# CAN_HB_PV_Heatpump.net
KiCad netlist of a schematic drawn in EAGLE
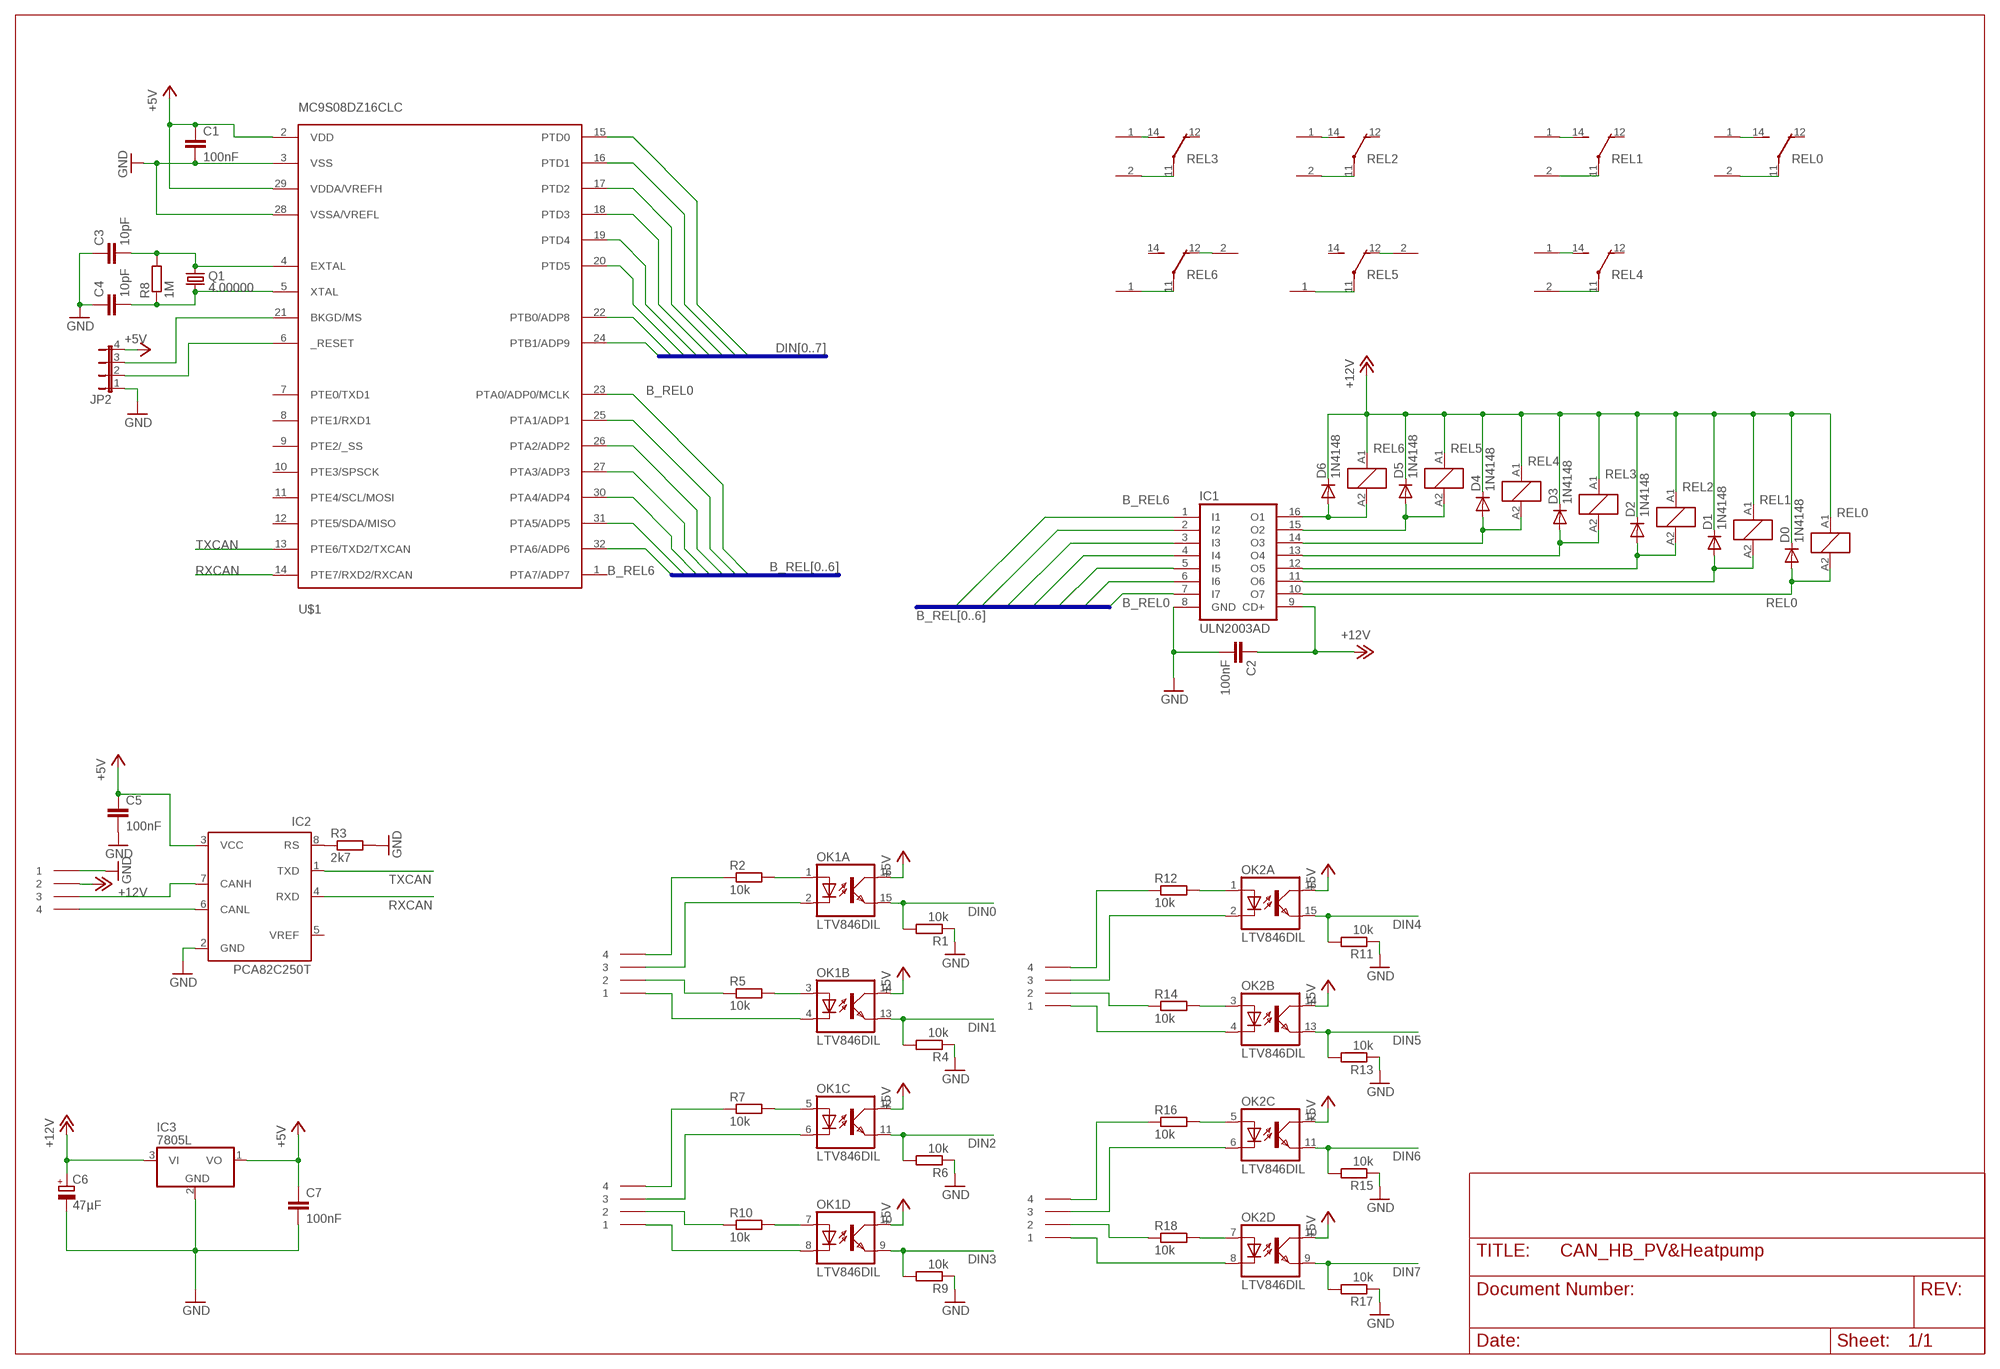
[diagram p0: schematic, sheet 1]

(export (version "E")
  (design (tool "Eeschema 10.0.6"))
  (components
    (comp (ref "C1")
      (value "100nF")
      (footprint "eagle-import:C0805K")
      (libsource (lib "eagle-import") (part "C-EUC0805K"))
    )
    (comp (ref "C2")
      (value "100nF")
      (footprint "eagle-import:C0805")
      (libsource (lib "eagle-import") (part "rcl_334_C-EUC0805"))
    )
    (comp (ref "C3")
      (value "10pF")
      (footprint "eagle-import:C0805K")
      (libsource (lib "eagle-import") (part "C-EUC0805K"))
    )
    (comp (ref "C4")
      (value "10pF")
      (footprint "eagle-import:C0805K")
      (libsource (lib "eagle-import") (part "C-EUC0805K"))
    )
    (comp (ref "C5")
      (value "100nF")
      (footprint "eagle-import:C0805")
      (libsource (lib "eagle-import") (part "C-EUC0805"))
    )
    (comp (ref "C6")
      (value "47µF")
      (footprint "eagle-import:E2-5")
      (libsource (lib "eagle-import") (part "CPOL-EUE2-5"))
    )
    (comp (ref "C7")
      (value "100nF")
      (footprint "eagle-import:C0805K")
      (libsource (lib "eagle-import") (part "C-EUC0805K"))
    )
    (comp (ref "D0")
      (value "1N4148")
      (footprint "eagle-import:SOD80C")
      (libsource (lib "eagle-import") (part "DIODE-SOD80C"))
    )
    (comp (ref "D1")
      (value "1N4148")
      (footprint "eagle-import:SOD80C")
      (libsource (lib "eagle-import") (part "DIODE-SOD80C"))
    )
    (comp (ref "D2")
      (value "1N4148")
      (footprint "eagle-import:SOD80C")
      (libsource (lib "eagle-import") (part "DIODE-SOD80C"))
    )
    (comp (ref "D3")
      (value "1N4148")
      (footprint "eagle-import:SOD80C")
      (libsource (lib "eagle-import") (part "DIODE-SOD80C"))
    )
    (comp (ref "D4")
      (value "1N4148")
      (footprint "eagle-import:SOD80C")
      (libsource (lib "eagle-import") (part "DIODE-SOD80C"))
    )
    (comp (ref "D5")
      (value "1N4148")
      (footprint "eagle-import:SOD80C")
      (libsource (lib "eagle-import") (part "DIODE-SOD80C"))
    )
    (comp (ref "D6")
      (value "1N4148")
      (footprint "eagle-import:SOD80C")
      (libsource (lib "eagle-import") (part "DIODE-SOD80C"))
    )
    (comp (ref "IC1")
      (value "ULN2003AD")
      (footprint "eagle-import:SO16")
      (libsource (lib "eagle-import") (part "ULN2003AD"))
    )
    (comp (ref "IC2")
      (value "PCA82C250T")
      (footprint "eagle-import:SO8")
      (libsource (lib "eagle-import") (part "PCA82C250T"))
    )
    (comp (ref "IC3")
      (value "7805L")
      (footprint "eagle-import:TO92")
      (libsource (lib "eagle-import") (part "78L05"))
    )
    (comp (ref "JP2")
      (value "JP4E")
      (footprint "eagle-import:JP4")
      (libsource (lib "eagle-import") (part "JP4E"))
    )
    (comp (ref "KL1")
      (value "AST021-04")
      (footprint "eagle-import:AST021-04")
      (libsource (lib "eagle-import") (part "AST021-04"))
    )
    (comp (ref "KL2")
      (value "AST021-04")
      (footprint "eagle-import:AST021-04")
      (libsource (lib "eagle-import") (part "AST021-04"))
    )
    (comp (ref "KL3")
      (value "AST021-04")
      (footprint "eagle-import:AST021-04")
      (libsource (lib "eagle-import") (part "AST021-04"))
    )
    (comp (ref "KL4")
      (value "AST021-04")
      (footprint "eagle-import:AST021-04")
      (libsource (lib "eagle-import") (part "AST021-04"))
    )
    (comp (ref "KL5")
      (value "AST021-04")
      (footprint "eagle-import:AST021-04")
      (libsource (lib "eagle-import") (part "AST021-04"))
    )
    (comp (ref "OK1")
      (value "LTV846DIL")
      (footprint "eagle-import:DIL16")
      (libsource (lib "eagle-import") (part "LTV846DIL"))
    )
    (comp (ref "OK2")
      (value "LTV846DIL")
      (footprint "eagle-import:DIL16")
      (libsource (lib "eagle-import") (part "LTV846DIL"))
    )
    (comp (ref "Q1")
      (value "4.00000")
      (footprint "eagle-import:HC49U-V")
      (libsource (lib "eagle-import") (part "CRYTALHC49U-V"))
    )
    (comp (ref "R1")
      (value "10k")
      (footprint "eagle-import:R0805")
      (libsource (lib "eagle-import") (part "rcl_334_R-EU_R0805"))
    )
    (comp (ref "R2")
      (value "10k")
      (footprint "eagle-import:R0805")
      (libsource (lib "eagle-import") (part "rcl_334_R-EU_R0805"))
    )
    (comp (ref "R3")
      (value "2k7")
      (footprint "eagle-import:R0805")
      (libsource (lib "eagle-import") (part "R-EU_R0805"))
    )
    (comp (ref "R4")
      (value "10k")
      (footprint "eagle-import:R0805")
      (libsource (lib "eagle-import") (part "rcl_334_R-EU_R0805"))
    )
    (comp (ref "R5")
      (value "10k")
      (footprint "eagle-import:R0805")
      (libsource (lib "eagle-import") (part "rcl_334_R-EU_R0805"))
    )
    (comp (ref "R6")
      (value "10k")
      (footprint "eagle-import:R0805")
      (libsource (lib "eagle-import") (part "rcl_334_R-EU_R0805"))
    )
    (comp (ref "R7")
      (value "10k")
      (footprint "eagle-import:R0805")
      (libsource (lib "eagle-import") (part "rcl_334_R-EU_R0805"))
    )
    (comp (ref "R8")
      (value "1M")
      (footprint "eagle-import:R0805")
      (libsource (lib "eagle-import") (part "R-EU_R0805"))
    )
    (comp (ref "R9")
      (value "10k")
      (footprint "eagle-import:R0805")
      (libsource (lib "eagle-import") (part "rcl_334_R-EU_R0805"))
    )
    (comp (ref "R10")
      (value "10k")
      (footprint "eagle-import:R0805")
      (libsource (lib "eagle-import") (part "rcl_334_R-EU_R0805"))
    )
    (comp (ref "R11")
      (value "10k")
      (footprint "eagle-import:R0805")
      (libsource (lib "eagle-import") (part "rcl_334_R-EU_R0805"))
    )
    (comp (ref "R12")
      (value "10k")
      (footprint "eagle-import:R0805")
      (libsource (lib "eagle-import") (part "rcl_334_R-EU_R0805"))
    )
    (comp (ref "R13")
      (value "10k")
      (footprint "eagle-import:R0805")
      (libsource (lib "eagle-import") (part "rcl_334_R-EU_R0805"))
    )
    (comp (ref "R14")
      (value "10k")
      (footprint "eagle-import:R0805")
      (libsource (lib "eagle-import") (part "rcl_334_R-EU_R0805"))
    )
    (comp (ref "R15")
      (value "10k")
      (footprint "eagle-import:R0805")
      (libsource (lib "eagle-import") (part "rcl_334_R-EU_R0805"))
    )
    (comp (ref "R16")
      (value "10k")
      (footprint "eagle-import:R0805")
      (libsource (lib "eagle-import") (part "rcl_334_R-EU_R0805"))
    )
    (comp (ref "R17")
      (value "10k")
      (footprint "eagle-import:R0805")
      (libsource (lib "eagle-import") (part "rcl_334_R-EU_R0805"))
    )
    (comp (ref "R18")
      (value "10k")
      (footprint "eagle-import:R0805")
      (libsource (lib "eagle-import") (part "rcl_334_R-EU_R0805"))
    )
    (comp (ref "REL0")
      (value "FIN34.51FIN34.51.7")
      (footprint "eagle-import:FIN34")
      (libsource (lib "eagle-import") (part "FIN34.51FIN34.51.7"))
    )
    (comp (ref "REL1")
      (value "FIN34.51FIN34.51.7")
      (footprint "eagle-import:FIN34")
      (libsource (lib "eagle-import") (part "FIN34.51FIN34.51.7"))
    )
    (comp (ref "REL2")
      (value "FIN34.51FIN34.51.7")
      (footprint "eagle-import:FIN34")
      (libsource (lib "eagle-import") (part "FIN34.51FIN34.51.7"))
    )
    (comp (ref "REL3")
      (value "FIN34.51FIN34.51.7")
      (footprint "eagle-import:FIN34")
      (libsource (lib "eagle-import") (part "FIN34.51FIN34.51.7"))
    )
    (comp (ref "REL4")
      (value "FIN34.51FIN34.51.7")
      (footprint "eagle-import:FIN34")
      (libsource (lib "eagle-import") (part "FIN34.51FIN34.51.7"))
    )
    (comp (ref "REL5")
      (value "FIN34.51FIN34.51.7")
      (footprint "eagle-import:FIN34")
      (libsource (lib "eagle-import") (part "FIN34.51FIN34.51.7"))
    )
    (comp (ref "REL6")
      (value "FIN34.51FIN34.51.7")
      (footprint "eagle-import:FIN34")
      (libsource (lib "eagle-import") (part "FIN34.51FIN34.51.7"))
    )
    (comp (ref "U$1")
      (value "MC9S08DZ16CLC")
      (footprint "eagle-import:LQFP32")
      (libsource (lib "eagle-import") (part "MC9S08DZ16CLC"))
    )
    (comp (ref "U$2")
      (value "AKL320-02")
      (footprint "eagle-import:AKL320-02")
      (libsource (lib "eagle-import") (part "AKL320-02"))
    )
    (comp (ref "U$3")
      (value "AKL320-02")
      (footprint "eagle-import:AKL320-02")
      (libsource (lib "eagle-import") (part "AKL320-02"))
    )
    (comp (ref "U$4")
      (value "AKL320-02")
      (footprint "eagle-import:AKL320-02")
      (libsource (lib "eagle-import") (part "AKL320-02"))
    )
    (comp (ref "U$5")
      (value "AKL320-02")
      (footprint "eagle-import:AKL320-02")
      (libsource (lib "eagle-import") (part "AKL320-02"))
    )
    (comp (ref "U$6")
      (value "AKL320-02")
      (footprint "eagle-import:AKL320-02")
      (libsource (lib "eagle-import") (part "AKL320-02"))
    )
    (comp (ref "U$14")
      (value "AKL320-02")
      (footprint "eagle-import:AKL320-02")
      (libsource (lib "eagle-import") (part "AKL320-02"))
    )
    (comp (ref "U$15")
      (value "AKL320-02")
      (footprint "eagle-import:AKL320-02")
      (libsource (lib "eagle-import") (part "AKL320-02"))
    )
  )
  (nets
    (net (code "1") (name "+5V") (class "Default")
      (node (ref "C1") (pin "1") (pinfunction "1_1") (pintype "passive"))
      (node (ref "C5") (pin "1") (pinfunction "1_1") (pintype "passive"))
      (node (ref "C7") (pin "1") (pinfunction "1_1") (pintype "passive"))
      (node (ref "IC2") (pin "3") (pinfunction "VCC_3") (pintype "power_in"))
      (node (ref "IC3") (pin "1") (pinfunction "VO_1") (pintype "passive"))
      (node (ref "JP2") (pin "4") (pinfunction "4_4") (pintype "passive"))
      (node (ref "OK1") (pin "10") (pinfunction "COL_10") (pintype "passive"))
      (node (ref "OK1") (pin "12") (pinfunction "COL_12") (pintype "passive"))
      (node (ref "OK1") (pin "14") (pinfunction "COL_14") (pintype "passive"))
      (node (ref "OK1") (pin "16") (pinfunction "COL_16") (pintype "passive"))
      (node (ref "OK2") (pin "10") (pinfunction "COL_10") (pintype "passive"))
      (node (ref "OK2") (pin "12") (pinfunction "COL_12") (pintype "passive"))
      (node (ref "OK2") (pin "14") (pinfunction "COL_14") (pintype "passive"))
      (node (ref "OK2") (pin "16") (pinfunction "COL_16") (pintype "passive"))
      (node (ref "U$1") (pin "2") (pinfunction "VDD_2") (pintype "power_in"))
      (node (ref "U$1") (pin "29") (pinfunction "VDDA/VREFH_29") (pintype "power_in"))
    )
    (net (code "2") (name "+12V") (class "Default")
      (node (ref "C2") (pin "1") (pinfunction "1_1") (pintype "passive"))
      (node (ref "C6") (pin "+") (pinfunction "+_+") (pintype "passive"))
      (node (ref "D0") (pin "C") (pinfunction "C_C") (pintype "passive"))
      (node (ref "D1") (pin "C") (pinfunction "C_C") (pintype "passive"))
      (node (ref "D2") (pin "C") (pinfunction "C_C") (pintype "passive"))
      (node (ref "D3") (pin "C") (pinfunction "C_C") (pintype "passive"))
      (node (ref "D4") (pin "C") (pinfunction "C_C") (pintype "passive"))
      (node (ref "D5") (pin "C") (pinfunction "C_C") (pintype "passive"))
      (node (ref "D6") (pin "C") (pinfunction "C_C") (pintype "passive"))
      (node (ref "IC1") (pin "9") (pinfunction "CD+_9") (pintype "passive"))
      (node (ref "IC3") (pin "3") (pinfunction "VI_3") (pintype "input"))
      (node (ref "KL1") (pin "P$2") (pinfunction "2_P$2") (pintype "bidirectional"))
      (node (ref "REL0") (pin "A1") (pinfunction "1_A1") (pintype "passive"))
      (node (ref "REL1") (pin "A1") (pinfunction "1_A1") (pintype "passive"))
      (node (ref "REL2") (pin "A1") (pinfunction "1_A1") (pintype "passive"))
      (node (ref "REL3") (pin "A1") (pinfunction "1_A1") (pintype "passive"))
      (node (ref "REL4") (pin "A1") (pinfunction "1_A1") (pintype "passive"))
      (node (ref "REL5") (pin "A1") (pinfunction "1_A1") (pintype "passive"))
      (node (ref "REL6") (pin "A1") (pinfunction "1_A1") (pintype "passive"))
    )
    (net (code "3") (name "/B_REL0") (class "Default")
      (node (ref "IC1") (pin "7") (pinfunction "I7_7") (pintype "input"))
      (node (ref "U$1") (pin "23") (pinfunction "PTA0/ADP0/MCLK_23") (pintype "bidirectional"))
    )
    (net (code "4") (name "/B_REL1") (class "Default")
      (node (ref "IC1") (pin "6") (pinfunction "I6_6") (pintype "input"))
      (node (ref "U$1") (pin "25") (pinfunction "PTA1/ADP1_25") (pintype "bidirectional"))
    )
    (net (code "5") (name "/B_REL2") (class "Default")
      (node (ref "IC1") (pin "5") (pinfunction "I5_5") (pintype "input"))
      (node (ref "U$1") (pin "26") (pinfunction "PTA2/ADP2_26") (pintype "bidirectional"))
    )
    (net (code "6") (name "/B_REL3") (class "Default")
      (node (ref "IC1") (pin "4") (pinfunction "I4_4") (pintype "input"))
      (node (ref "U$1") (pin "27") (pinfunction "PTA3/ADP3_27") (pintype "bidirectional"))
    )
    (net (code "7") (name "/B_REL4") (class "Default")
      (node (ref "IC1") (pin "3") (pinfunction "I3_3") (pintype "input"))
      (node (ref "U$1") (pin "30") (pinfunction "PTA4/ADP4_30") (pintype "bidirectional"))
    )
    (net (code "8") (name "/B_REL5") (class "Default")
      (node (ref "IC1") (pin "2") (pinfunction "I2_2") (pintype "input"))
      (node (ref "U$1") (pin "31") (pinfunction "PTA5/ADP5_31") (pintype "bidirectional"))
    )
    (net (code "9") (name "/B_REL6") (class "Default")
      (node (ref "IC1") (pin "1") (pinfunction "I1_1") (pintype "input"))
      (node (ref "U$1") (pin "32") (pinfunction "PTA6/ADP6_32") (pintype "bidirectional"))
    )
    (net (code "11") (name "/DIN0") (class "Default")
      (node (ref "OK1") (pin "15") (pinfunction "EMIT_15") (pintype "passive"))
      (node (ref "R1") (pin "2") (pinfunction "2_2") (pintype "passive"))
      (node (ref "U$1") (pin "15") (pinfunction "PTD0_15") (pintype "bidirectional"))
    )
    (net (code "12") (name "/DIN1") (class "Default")
      (node (ref "OK1") (pin "13") (pinfunction "EMIT_13") (pintype "passive"))
      (node (ref "R4") (pin "2") (pinfunction "2_2") (pintype "passive"))
      (node (ref "U$1") (pin "16") (pinfunction "PTD1_16") (pintype "bidirectional"))
    )
    (net (code "13") (name "/DIN2") (class "Default")
      (node (ref "OK1") (pin "11") (pinfunction "EMIT_11") (pintype "passive"))
      (node (ref "R6") (pin "2") (pinfunction "2_2") (pintype "passive"))
      (node (ref "U$1") (pin "17") (pinfunction "PTD2_17") (pintype "bidirectional"))
    )
    (net (code "14") (name "/DIN3") (class "Default")
      (node (ref "OK1") (pin "9") (pinfunction "EMIT_9") (pintype "passive"))
      (node (ref "R9") (pin "2") (pinfunction "2_2") (pintype "passive"))
      (node (ref "U$1") (pin "18") (pinfunction "PTD3_18") (pintype "bidirectional"))
    )
    (net (code "15") (name "/DIN4") (class "Default")
      (node (ref "OK2") (pin "15") (pinfunction "EMIT_15") (pintype "passive"))
      (node (ref "R11") (pin "2") (pinfunction "2_2") (pintype "passive"))
      (node (ref "U$1") (pin "19") (pinfunction "PTD4_19") (pintype "bidirectional"))
    )
    (net (code "16") (name "/DIN5") (class "Default")
      (node (ref "OK2") (pin "13") (pinfunction "EMIT_13") (pintype "passive"))
      (node (ref "R13") (pin "2") (pinfunction "2_2") (pintype "passive"))
      (node (ref "U$1") (pin "20") (pinfunction "PTD5_20") (pintype "bidirectional"))
    )
    (net (code "17") (name "/DIN6") (class "Default")
      (node (ref "OK2") (pin "11") (pinfunction "EMIT_11") (pintype "passive"))
      (node (ref "R15") (pin "2") (pinfunction "2_2") (pintype "passive"))
      (node (ref "U$1") (pin "22") (pinfunction "PTB0/ADP8_22") (pintype "bidirectional"))
    )
    (net (code "18") (name "/DIN7") (class "Default")
      (node (ref "OK2") (pin "9") (pinfunction "EMIT_9") (pintype "passive"))
      (node (ref "R17") (pin "2") (pinfunction "2_2") (pintype "passive"))
      (node (ref "U$1") (pin "24") (pinfunction "PTB1/ADP9_24") (pintype "bidirectional"))
    )
    (net (code "20") (name "/REL0") (class "Default")
      (node (ref "D0") (pin "A") (pinfunction "A_A") (pintype "passive"))
      (node (ref "IC1") (pin "10") (pinfunction "O7_10") (pintype "open_collector"))
      (node (ref "REL0") (pin "A2") (pinfunction "2_A2") (pintype "passive"))
    )
    (net (code "21") (name "/RXCAN") (class "Default")
      (node (ref "IC2") (pin "4") (pinfunction "RXD_4") (pintype "output"))
      (node (ref "U$1") (pin "14") (pinfunction "PTE7/RXD2/RXCAN_14") (pintype "input"))
    )
    (net (code "22") (name "/TXCAN") (class "Default")
      (node (ref "IC2") (pin "1") (pinfunction "TXD_1") (pintype "input"))
      (node (ref "U$1") (pin "13") (pinfunction "PTE6/TXD2/TXCAN_13") (pintype "output"))
    )
    (net (code "23") (name "GND") (class "Default")
      (node (ref "C1") (pin "2") (pinfunction "2_2") (pintype "passive"))
      (node (ref "C2") (pin "2") (pinfunction "2_2") (pintype "passive"))
      (node (ref "C3") (pin "1") (pinfunction "1_1") (pintype "passive"))
      (node (ref "C4") (pin "1") (pinfunction "1_1") (pintype "passive"))
      (node (ref "C5") (pin "2") (pinfunction "2_2") (pintype "passive"))
      (node (ref "C6") (pin "-") (pinfunction "-_-") (pintype "passive"))
      (node (ref "C7") (pin "2") (pinfunction "2_2") (pintype "passive"))
      (node (ref "IC1") (pin "8") (pinfunction "GND_8") (pintype "power_in"))
      (node (ref "IC2") (pin "2") (pinfunction "GND_2") (pintype "power_in"))
      (node (ref "IC3") (pin "2") (pinfunction "GND_2") (pintype "passive"))
      (node (ref "JP2") (pin "1") (pinfunction "1_1") (pintype "passive"))
      (node (ref "KL1") (pin "P$1") (pinfunction "1_P$1") (pintype "bidirectional"))
      (node (ref "R1") (pin "1") (pinfunction "1_1") (pintype "passive"))
      (node (ref "R11") (pin "1") (pinfunction "1_1") (pintype "passive"))
      (node (ref "R13") (pin "1") (pinfunction "1_1") (pintype "passive"))
      (node (ref "R15") (pin "1") (pinfunction "1_1") (pintype "passive"))
      (node (ref "R17") (pin "1") (pinfunction "1_1") (pintype "passive"))
      (node (ref "R3") (pin "2") (pinfunction "2_2") (pintype "passive"))
      (node (ref "R4") (pin "1") (pinfunction "1_1") (pintype "passive"))
      (node (ref "R6") (pin "1") (pinfunction "1_1") (pintype "passive"))
      (node (ref "R9") (pin "1") (pinfunction "1_1") (pintype "passive"))
      (node (ref "U$1") (pin "28") (pinfunction "VSSA/VREFL_28") (pintype "power_in"))
      (node (ref "U$1") (pin "3") (pinfunction "VSS_3") (pintype "power_in"))
    )
    (net (code "24") (name "Net-(IC1-O1)") (class "Default")
      (node (ref "D6") (pin "A") (pinfunction "A_A") (pintype "passive"))
      (node (ref "IC1") (pin "16") (pinfunction "O1_16") (pintype "open_collector"))
      (node (ref "REL6") (pin "A2") (pinfunction "2_A2") (pintype "passive"))
    )
    (net (code "25") (name "Net-(IC1-O2)") (class "Default")
      (node (ref "D5") (pin "A") (pinfunction "A_A") (pintype "passive"))
      (node (ref "IC1") (pin "15") (pinfunction "O2_15") (pintype "open_collector"))
      (node (ref "REL5") (pin "A2") (pinfunction "2_A2") (pintype "passive"))
    )
    (net (code "26") (name "Net-(IC1-O3)") (class "Default")
      (node (ref "D4") (pin "A") (pinfunction "A_A") (pintype "passive"))
      (node (ref "IC1") (pin "14") (pinfunction "O3_14") (pintype "open_collector"))
      (node (ref "REL4") (pin "A2") (pinfunction "2_A2") (pintype "passive"))
    )
    (net (code "27") (name "Net-(IC1-O4)") (class "Default")
      (node (ref "D3") (pin "A") (pinfunction "A_A") (pintype "passive"))
      (node (ref "IC1") (pin "13") (pinfunction "O4_13") (pintype "open_collector"))
      (node (ref "REL3") (pin "A2") (pinfunction "2_A2") (pintype "passive"))
    )
    (net (code "28") (name "Net-(IC1-O5)") (class "Default")
      (node (ref "D2") (pin "A") (pinfunction "A_A") (pintype "passive"))
      (node (ref "IC1") (pin "12") (pinfunction "O5_12") (pintype "open_collector"))
      (node (ref "REL2") (pin "A2") (pinfunction "2_A2") (pintype "passive"))
    )
    (net (code "29") (name "Net-(IC1-O6)") (class "Default")
      (node (ref "D1") (pin "A") (pinfunction "A_A") (pintype "passive"))
      (node (ref "IC1") (pin "11") (pinfunction "O6_11") (pintype "open_collector"))
      (node (ref "REL1") (pin "A2") (pinfunction "2_A2") (pintype "passive"))
    )
    (net (code "30") (name "Net-(IC2-CANH)") (class "Default")
      (node (ref "IC2") (pin "7") (pinfunction "CANH_7") (pintype "bidirectional"))
      (node (ref "KL1") (pin "P$3") (pinfunction "3_P$3") (pintype "bidirectional"))
    )
    (net (code "31") (name "Net-(IC2-CANL)") (class "Default")
      (node (ref "IC2") (pin "6") (pinfunction "CANL_6") (pintype "bidirectional"))
      (node (ref "KL1") (pin "P$4") (pinfunction "4_P$4") (pintype "bidirectional"))
    )
    (net (code "32") (name "Net-(IC2-RS)") (class "Default")
      (node (ref "IC2") (pin "8") (pinfunction "RS_8") (pintype "input"))
      (node (ref "R3") (pin "1") (pinfunction "1_1") (pintype "passive"))
    )
    (net (code "33") (name "Net-(KL2-1)") (class "Default")
      (node (ref "KL2") (pin "P$1") (pinfunction "1_P$1") (pintype "bidirectional"))
      (node (ref "OK1") (pin "4") (pinfunction "C_4") (pintype "passive"))
    )
    (net (code "34") (name "Net-(KL2-2)") (class "Default")
      (node (ref "KL2") (pin "P$2") (pinfunction "2_P$2") (pintype "bidirectional"))
      (node (ref "R5") (pin "1") (pinfunction "1_1") (pintype "passive"))
    )
    (net (code "35") (name "Net-(KL2-3)") (class "Default")
      (node (ref "KL2") (pin "P$3") (pinfunction "3_P$3") (pintype "bidirectional"))
      (node (ref "OK1") (pin "2") (pinfunction "C_2") (pintype "passive"))
    )
    (net (code "36") (name "Net-(KL2-4)") (class "Default")
      (node (ref "KL2") (pin "P$4") (pinfunction "4_P$4") (pintype "bidirectional"))
      (node (ref "R2") (pin "1") (pinfunction "1_1") (pintype "passive"))
    )
    (net (code "37") (name "Net-(KL3-1)") (class "Default")
      (node (ref "KL3") (pin "P$1") (pinfunction "1_P$1") (pintype "bidirectional"))
      (node (ref "OK1") (pin "8") (pinfunction "C_8") (pintype "passive"))
    )
    (net (code "38") (name "Net-(KL3-2)") (class "Default")
      (node (ref "KL3") (pin "P$2") (pinfunction "2_P$2") (pintype "bidirectional"))
      (node (ref "R10") (pin "1") (pinfunction "1_1") (pintype "passive"))
    )
    (net (code "39") (name "Net-(KL3-3)") (class "Default")
      (node (ref "KL3") (pin "P$3") (pinfunction "3_P$3") (pintype "bidirectional"))
      (node (ref "OK1") (pin "6") (pinfunction "C_6") (pintype "passive"))
    )
    (net (code "40") (name "Net-(KL3-4)") (class "Default")
      (node (ref "KL3") (pin "P$4") (pinfunction "4_P$4") (pintype "bidirectional"))
      (node (ref "R7") (pin "1") (pinfunction "1_1") (pintype "passive"))
    )
    (net (code "41") (name "Net-(KL4-1)") (class "Default")
      (node (ref "KL4") (pin "P$1") (pinfunction "1_P$1") (pintype "bidirectional"))
      (node (ref "OK2") (pin "4") (pinfunction "C_4") (pintype "passive"))
    )
    (net (code "42") (name "Net-(KL4-2)") (class "Default")
      (node (ref "KL4") (pin "P$2") (pinfunction "2_P$2") (pintype "bidirectional"))
      (node (ref "R14") (pin "1") (pinfunction "1_1") (pintype "passive"))
    )
    (net (code "43") (name "Net-(KL4-3)") (class "Default")
      (node (ref "KL4") (pin "P$3") (pinfunction "3_P$3") (pintype "bidirectional"))
      (node (ref "OK2") (pin "2") (pinfunction "C_2") (pintype "passive"))
    )
    (net (code "44") (name "Net-(KL4-4)") (class "Default")
      (node (ref "KL4") (pin "P$4") (pinfunction "4_P$4") (pintype "bidirectional"))
      (node (ref "R12") (pin "1") (pinfunction "1_1") (pintype "passive"))
    )
    (net (code "45") (name "Net-(KL5-1)") (class "Default")
      (node (ref "KL5") (pin "P$1") (pinfunction "1_P$1") (pintype "bidirectional"))
      (node (ref "OK2") (pin "8") (pinfunction "C_8") (pintype "passive"))
    )
    (net (code "46") (name "Net-(KL5-2)") (class "Default")
      (node (ref "KL5") (pin "P$2") (pinfunction "2_P$2") (pintype "bidirectional"))
      (node (ref "R18") (pin "1") (pinfunction "1_1") (pintype "passive"))
    )
    (net (code "47") (name "Net-(KL5-3)") (class "Default")
      (node (ref "KL5") (pin "P$3") (pinfunction "3_P$3") (pintype "bidirectional"))
      (node (ref "OK2") (pin "6") (pinfunction "C_6") (pintype "passive"))
    )
    (net (code "48") (name "Net-(KL5-4)") (class "Default")
      (node (ref "KL5") (pin "P$4") (pinfunction "4_P$4") (pintype "bidirectional"))
      (node (ref "R16") (pin "1") (pinfunction "1_1") (pintype "passive"))
    )
    (net (code "49") (name "Net-(OK1A-A)") (class "Default")
      (node (ref "OK1") (pin "1") (pinfunction "A_1") (pintype "passive"))
      (node (ref "R2") (pin "2") (pinfunction "2_2") (pintype "passive"))
    )
    (net (code "50") (name "Net-(OK1B-A)") (class "Default")
      (node (ref "OK1") (pin "3") (pinfunction "A_3") (pintype "passive"))
      (node (ref "R5") (pin "2") (pinfunction "2_2") (pintype "passive"))
    )
    (net (code "51") (name "Net-(OK1C-A)") (class "Default")
      (node (ref "OK1") (pin "5") (pinfunction "A_5") (pintype "passive"))
      (node (ref "R7") (pin "2") (pinfunction "2_2") (pintype "passive"))
    )
    (net (code "52") (name "Net-(OK1D-A)") (class "Default")
      (node (ref "OK1") (pin "7") (pinfunction "A_7") (pintype "passive"))
      (node (ref "R10") (pin "2") (pinfunction "2_2") (pintype "passive"))
    )
    (net (code "53") (name "Net-(OK2A-A)") (class "Default")
      (node (ref "OK2") (pin "1") (pinfunction "A_1") (pintype "passive"))
      (node (ref "R12") (pin "2") (pinfunction "2_2") (pintype "passive"))
    )
    (net (code "54") (name "Net-(OK2B-A)") (class "Default")
      (node (ref "OK2") (pin "3") (pinfunction "A_3") (pintype "passive"))
      (node (ref "R14") (pin "2") (pinfunction "2_2") (pintype "passive"))
    )
    (net (code "55") (name "Net-(OK2C-A)") (class "Default")
      (node (ref "OK2") (pin "5") (pinfunction "A_5") (pintype "passive"))
      (node (ref "R16") (pin "2") (pinfunction "2_2") (pintype "passive"))
    )
    (net (code "56") (name "Net-(OK2D-A)") (class "Default")
      (node (ref "OK2") (pin "7") (pinfunction "A_7") (pintype "passive"))
      (node (ref "R18") (pin "2") (pinfunction "2_2") (pintype "passive"))
    )
    (net (code "57") (name "Net-(REL0B-P)") (class "Default")
      (node (ref "REL0") (pin "11") (pinfunction "P_11") (pintype "passive"))
      (node (ref "U$15") (pin "2") (pinfunction "P$1_2") (pintype "bidirectional"))
    )
    (net (code "58") (name "Net-(REL0B-S)") (class "Default")
      (node (ref "REL0") (pin "14") (pinfunction "S_14") (pintype "passive"))
      (node (ref "U$15") (pin "1") (pinfunction "P$1_1") (pintype "bidirectional"))
    )
    (net (code "59") (name "Net-(REL1B-P)") (class "Default")
      (node (ref "REL1") (pin "11") (pinfunction "P_11") (pintype "passive"))
      (node (ref "U$6") (pin "2") (pinfunction "P$1_2") (pintype "bidirectional"))
    )
    (net (code "60") (name "Net-(REL1B-S)") (class "Default")
      (node (ref "REL1") (pin "14") (pinfunction "S_14") (pintype "passive"))
      (node (ref "U$6") (pin "1") (pinfunction "P$1_1") (pintype "bidirectional"))
    )
    (net (code "61") (name "Net-(REL2B-P)") (class "Default")
      (node (ref "REL2") (pin "11") (pinfunction "P_11") (pintype "passive"))
      (node (ref "U$4") (pin "2") (pinfunction "P$1_2") (pintype "bidirectional"))
    )
    (net (code "62") (name "Net-(REL2B-S)") (class "Default")
      (node (ref "REL2") (pin "14") (pinfunction "S_14") (pintype "passive"))
      (node (ref "U$4") (pin "1") (pinfunction "P$1_1") (pintype "bidirectional"))
    )
    (net (code "63") (name "Net-(REL3B-P)") (class "Default")
      (node (ref "REL3") (pin "11") (pinfunction "P_11") (pintype "passive"))
      (node (ref "U$2") (pin "2") (pinfunction "P$1_2") (pintype "bidirectional"))
    )
    (net (code "64") (name "Net-(REL3B-S)") (class "Default")
      (node (ref "REL3") (pin "14") (pinfunction "S_14") (pintype "passive"))
      (node (ref "U$2") (pin "1") (pinfunction "P$1_1") (pintype "bidirectional"))
    )
    (net (code "65") (name "Net-(REL4B-P)") (class "Default")
      (node (ref "REL4") (pin "11") (pinfunction "P_11") (pintype "passive"))
      (node (ref "U$14") (pin "2") (pinfunction "P$1_2") (pintype "bidirectional"))
    )
    (net (code "66") (name "Net-(REL4B-S)") (class "Default")
      (node (ref "REL4") (pin "14") (pinfunction "S_14") (pintype "passive"))
      (node (ref "U$14") (pin "1") (pinfunction "P$1_1") (pintype "bidirectional"))
    )
    (net (code "67") (name "Net-(REL5B-O)") (class "Default")
      (node (ref "REL5") (pin "12") (pinfunction "O_12") (pintype "passive"))
      (node (ref "U$5") (pin "2") (pinfunction "P$1_2") (pintype "bidirectional"))
    )
    (net (code "68") (name "Net-(REL5B-P)") (class "Default")
      (node (ref "REL5") (pin "11") (pinfunction "P_11") (pintype "passive"))
      (node (ref "U$5") (pin "1") (pinfunction "P$1_1") (pintype "bidirectional"))
    )
    (net (code "69") (name "Net-(REL6B-O)") (class "Default")
      (node (ref "REL6") (pin "12") (pinfunction "O_12") (pintype "passive"))
      (node (ref "U$3") (pin "2") (pinfunction "P$1_2") (pintype "bidirectional"))
    )
    (net (code "70") (name "Net-(REL6B-P)") (class "Default")
      (node (ref "REL6") (pin "11") (pinfunction "P_11") (pintype "passive"))
      (node (ref "U$3") (pin "1") (pinfunction "P$1_1") (pintype "bidirectional"))
    )
    (net (code "71") (name "Net-(U$1-BKGD{slash}MS)") (class "Default")
      (node (ref "JP2") (pin "3") (pinfunction "3_3") (pintype "passive"))
      (node (ref "U$1") (pin "21") (pinfunction "BKGD/MS_21") (pintype "bidirectional"))
    )
    (net (code "72") (name "Net-(U$1-EXTAL)") (class "Default")
      (node (ref "C3") (pin "2") (pinfunction "2_2") (pintype "passive"))
      (node (ref "Q1") (pin "2") (pinfunction "2_2") (pintype "passive"))
      (node (ref "R8") (pin "2") (pinfunction "2_2") (pintype "passive"))
      (node (ref "U$1") (pin "4") (pinfunction "EXTAL_4") (pintype "bidirectional"))
    )
    (net (code "73") (name "Net-(U$1-XTAL)") (class "Default")
      (node (ref "C4") (pin "2") (pinfunction "2_2") (pintype "passive"))
      (node (ref "Q1") (pin "1") (pinfunction "1_1") (pintype "passive"))
      (node (ref "R8") (pin "1") (pinfunction "1_1") (pintype "passive"))
      (node (ref "U$1") (pin "5") (pinfunction "XTAL_5") (pintype "bidirectional"))
    )
    (net (code "74") (name "Net-(U$1-_RESET)") (class "Default")
      (node (ref "JP2") (pin "2") (pinfunction "2_2") (pintype "passive"))
      (node (ref "U$1") (pin "6") (pinfunction "_RESET_6") (pintype "bidirectional"))
    )
    (net (code "75") (name "unconnected-(IC2-VREF-Pad5)") (class "Default")
      (node (ref "IC2") (pin "5") (pinfunction "VREF_5") (pintype "output"))
    )
    (net (code "76") (name "unconnected-(REL0B-O-Pad12)") (class "Default")
      (node (ref "REL0") (pin "12") (pinfunction "O_12") (pintype "passive"))
    )
    (net (code "77") (name "unconnected-(REL1B-O-Pad12)") (class "Default")
      (node (ref "REL1") (pin "12") (pinfunction "O_12") (pintype "passive"))
    )
    (net (code "78") (name "unconnected-(REL2B-O-Pad12)") (class "Default")
      (node (ref "REL2") (pin "12") (pinfunction "O_12") (pintype "passive"))
    )
    (net (code "79") (name "unconnected-(REL3B-O-Pad12)") (class "Default")
      (node (ref "REL3") (pin "12") (pinfunction "O_12") (pintype "passive"))
    )
    (net (code "80") (name "unconnected-(REL4B-O-Pad12)") (class "Default")
      (node (ref "REL4") (pin "12") (pinfunction "O_12") (pintype "passive"))
    )
    (net (code "81") (name "unconnected-(REL5B-S-Pad14)") (class "Default")
      (node (ref "REL5") (pin "14") (pinfunction "S_14") (pintype "passive"))
    )
    (net (code "82") (name "unconnected-(REL6B-S-Pad14)") (class "Default")
      (node (ref "REL6") (pin "14") (pinfunction "S_14") (pintype "passive"))
    )
    (net (code "83") (name "unconnected-(U$1-PTA7{slash}ADP7-Pad1)") (class "Default")
      (node (ref "U$1") (pin "1") (pinfunction "PTA7/ADP7_1") (pintype "bidirectional"))
    )
    (net (code "84") (name "unconnected-(U$1-PTE0{slash}TXD1-Pad7)") (class "Default")
      (node (ref "U$1") (pin "7") (pinfunction "PTE0/TXD1_7") (pintype "bidirectional"))
    )
    (net (code "85") (name "unconnected-(U$1-PTE1{slash}RXD1-Pad8)") (class "Default")
      (node (ref "U$1") (pin "8") (pinfunction "PTE1/RXD1_8") (pintype "bidirectional"))
    )
    (net (code "86") (name "unconnected-(U$1-PTE2{slash}_SS-Pad9)") (class "Default")
      (node (ref "U$1") (pin "9") (pinfunction "PTE2/_SS_9") (pintype "bidirectional"))
    )
    (net (code "87") (name "unconnected-(U$1-PTE3{slash}SPSCK-Pad10)") (class "Default")
      (node (ref "U$1") (pin "10") (pinfunction "PTE3/SPSCK_10") (pintype "bidirectional"))
    )
    (net (code "88") (name "unconnected-(U$1-PTE4{slash}SCL{slash}MOSI-Pad11)") (class "Default")
      (node (ref "U$1") (pin "11") (pinfunction "PTE4/SCL/MOSI_11") (pintype "bidirectional"))
    )
    (net (code "89") (name "unconnected-(U$1-PTE5{slash}SDA{slash}MISO-Pad12)") (class "Default")
      (node (ref "U$1") (pin "12") (pinfunction "PTE5/SDA/MISO_12") (pintype "bidirectional"))
    )
  )
)
